# repeater2.net
KiCad netlist of a schematic drawn in EAGLE
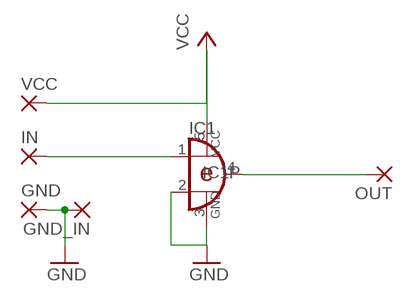
[diagram p0: schematic, sheet 1]

(export (version "E")
  (design (tool "Eeschema 10.0.6"))
  (components
    (comp (ref "GND")
      (value "SMD2")
      (footprint "eagle-import:SMD1,27-2,54")
      (libsource (lib "eagle-import") (part "SMD2"))
    )
    (comp (ref "GND_IN")
      (value "SMD2")
      (footprint "eagle-import:SMD1,27-2,54")
      (libsource (lib "eagle-import") (part "SMD2"))
    )
    (comp (ref "IC1")
      (value "74AHC1G86DCK")
      (footprint "eagle-import:SC70-5")
      (libsource (lib "eagle-import") (part "741G86DCKAHC"))
    )
    (comp (ref "IN")
      (value "SMD2")
      (footprint "eagle-import:SMD1,27-2,54")
      (libsource (lib "eagle-import") (part "SMD2"))
    )
    (comp (ref "OUT")
      (value "SMD2")
      (footprint "eagle-import:SMD1,27-2,54")
      (libsource (lib "eagle-import") (part "SMD2"))
    )
    (comp (ref "VCC")
      (value "SMD2")
      (footprint "eagle-import:SMD1,27-2,54")
      (libsource (lib "eagle-import") (part "SMD2"))
    )
  )
  (nets
    (net (code "1") (name "GND") (class "Default")
      (node (ref "GND") (pin "1") (pinfunction "P_1") (pintype "passive"))
      (node (ref "GND_IN") (pin "1") (pinfunction "P_1") (pintype "passive"))
      (node (ref "IC1") (pin "2") (pinfunction "I1_2") (pintype "input"))
      (node (ref "IC1") (pin "3") (pinfunction "GND_3") (pintype "power_in"))
    )
    (net (code "2") (name "Net-(IC1A-I0)") (class "Default")
      (node (ref "IC1") (pin "1") (pinfunction "I0_1") (pintype "input"))
      (node (ref "IN") (pin "1") (pinfunction "P_1") (pintype "passive"))
    )
    (net (code "3") (name "Net-(IC1A-O)") (class "Default")
      (node (ref "IC1") (pin "4") (pinfunction "O_4") (pintype "output"))
      (node (ref "OUT") (pin "1") (pinfunction "P_1") (pintype "passive"))
    )
    (net (code "4") (name "VCC") (class "Default")
      (node (ref "IC1") (pin "5") (pinfunction "VCC_5") (pintype "power_in"))
      (node (ref "VCC") (pin "1") (pinfunction "P_1") (pintype "passive"))
    )
  )
)
